# RC_module.net
KiCad netlist of a schematic drawn in EAGLE
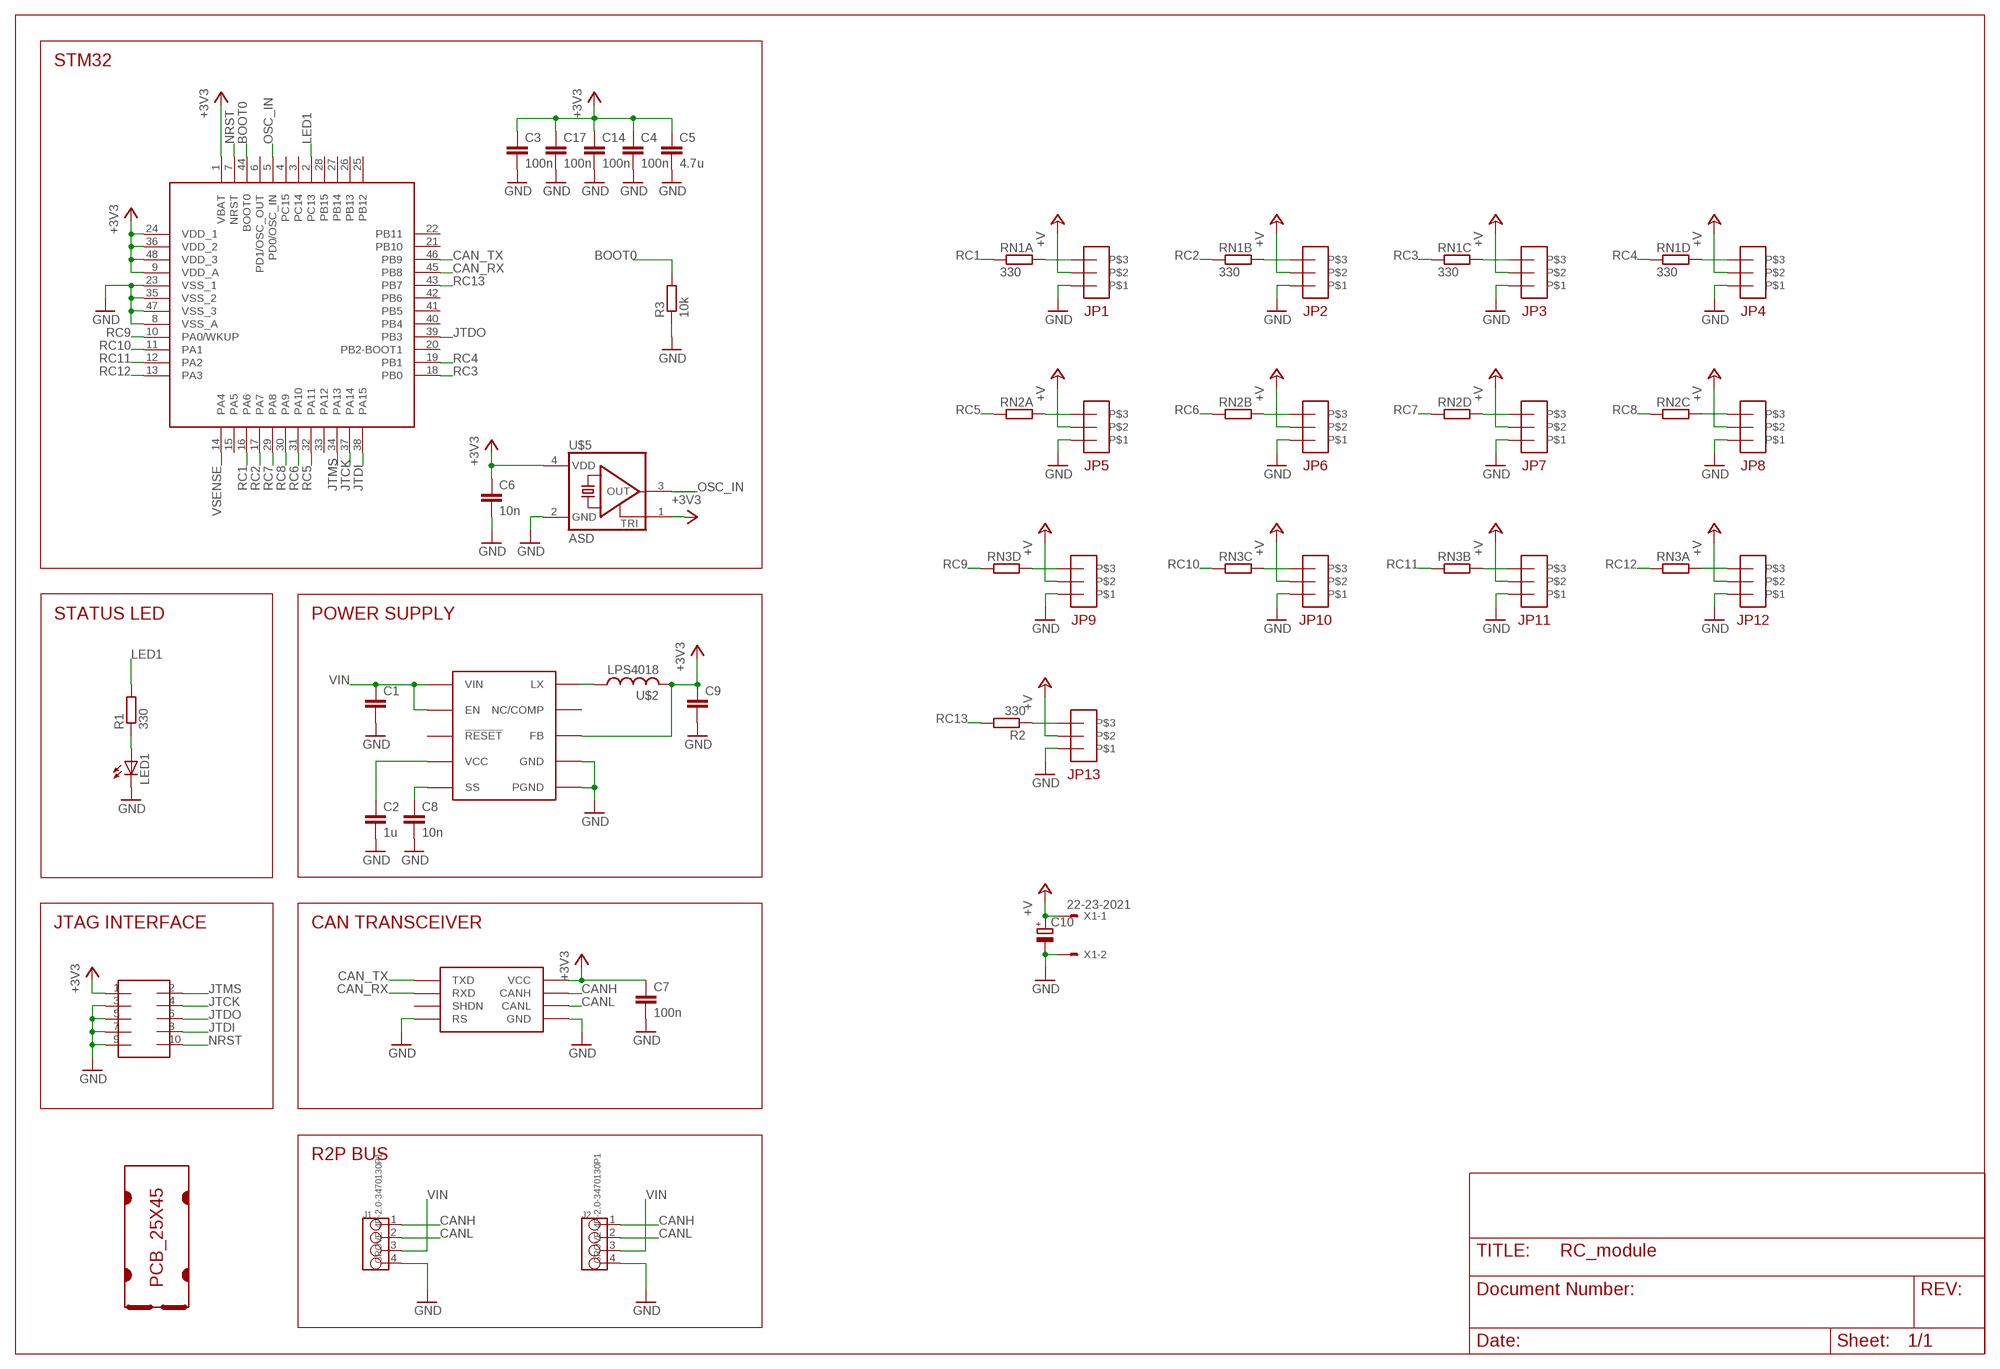
[diagram p0: schematic, sheet 1]

(export (version "E")
  (design (tool "Eeschema 10.0.6"))
  (components
    (comp (ref "C1")
      (value "C-EUC1206")
      (footprint "eagle-import:C1206")
      (libsource (lib "eagle-import") (part "C-EUC1206"))
    )
    (comp (ref "C2")
      (value "1u")
      (footprint "eagle-import:C0603")
      (libsource (lib "eagle-import") (part "C-EUC0603"))
    )
    (comp (ref "C3")
      (value "100n")
      (footprint "eagle-import:C0603")
      (libsource (lib "eagle-import") (part "C-EUC0603"))
    )
    (comp (ref "C4")
      (value "100n")
      (footprint "eagle-import:C0603")
      (libsource (lib "eagle-import") (part "C-EUC0603"))
    )
    (comp (ref "C5")
      (value "4.7u")
      (footprint "eagle-import:C0805")
      (libsource (lib "eagle-import") (part "C-EUC0805"))
    )
    (comp (ref "C6")
      (value "10n")
      (footprint "eagle-import:C0603")
      (libsource (lib "eagle-import") (part "C-EUC0603"))
    )
    (comp (ref "C7")
      (value "100n")
      (footprint "eagle-import:C0603")
      (libsource (lib "eagle-import") (part "C-EUC0603"))
    )
    (comp (ref "C8")
      (value "10n")
      (footprint "eagle-import:C0603")
      (libsource (lib "eagle-import") (part "C-EUC0603"))
    )
    (comp (ref "C9")
      (value "C-EUC0805")
      (footprint "eagle-import:C0805")
      (libsource (lib "eagle-import") (part "C-EUC0805"))
    )
    (comp (ref "C10")
      (value "CPOL-EUB/3528-21R")
      (footprint "eagle-import:B_3528-21R")
      (libsource (lib "eagle-import") (part "CPOL-EUB/3528-21R"))
    )
    (comp (ref "C14")
      (value "100n")
      (footprint "eagle-import:C0603")
      (libsource (lib "eagle-import") (part "C-EUC0603"))
    )
    (comp (ref "C17")
      (value "100n")
      (footprint "eagle-import:C0603")
      (libsource (lib "eagle-import") (part "C-EUC0603"))
    )
    (comp (ref "J1")
      (value "GROVE-4P-2.0-3470130P1")
      (footprint "eagle-import:4P-2.0")
      (libsource (lib "eagle-import") (part "GROVE-4P-2.0-3470130P1"))
    )
    (comp (ref "J2")
      (value "GROVE-4P-2.0-3470130P1")
      (footprint "eagle-import:4P-2.0")
      (libsource (lib "eagle-import") (part "GROVE-4P-2.0-3470130P1"))
    )
    (comp (ref "JP1")
      (value "PINHD-3")
      (footprint "eagle-import:1X03")
      (libsource (lib "eagle-import") (part "PINHD-3"))
    )
    (comp (ref "JP2")
      (value "PINHD-3")
      (footprint "eagle-import:1X03")
      (libsource (lib "eagle-import") (part "PINHD-3"))
    )
    (comp (ref "JP3")
      (value "PINHD-3")
      (footprint "eagle-import:1X03")
      (libsource (lib "eagle-import") (part "PINHD-3"))
    )
    (comp (ref "JP4")
      (value "PINHD-3")
      (footprint "eagle-import:1X03")
      (libsource (lib "eagle-import") (part "PINHD-3"))
    )
    (comp (ref "JP5")
      (value "PINHD-3")
      (footprint "eagle-import:1X03")
      (libsource (lib "eagle-import") (part "PINHD-3"))
    )
    (comp (ref "JP6")
      (value "PINHD-3")
      (footprint "eagle-import:1X03")
      (libsource (lib "eagle-import") (part "PINHD-3"))
    )
    (comp (ref "JP7")
      (value "PINHD-3")
      (footprint "eagle-import:1X03")
      (libsource (lib "eagle-import") (part "PINHD-3"))
    )
    (comp (ref "JP8")
      (value "PINHD-3")
      (footprint "eagle-import:1X03")
      (libsource (lib "eagle-import") (part "PINHD-3"))
    )
    (comp (ref "JP9")
      (value "PINHD-3")
      (footprint "eagle-import:1X03")
      (libsource (lib "eagle-import") (part "PINHD-3"))
    )
    (comp (ref "JP10")
      (value "PINHD-3")
      (footprint "eagle-import:1X03")
      (libsource (lib "eagle-import") (part "PINHD-3"))
    )
    (comp (ref "JP11")
      (value "PINHD-3")
      (footprint "eagle-import:1X03")
      (libsource (lib "eagle-import") (part "PINHD-3"))
    )
    (comp (ref "JP12")
      (value "PINHD-3")
      (footprint "eagle-import:1X03")
      (libsource (lib "eagle-import") (part "PINHD-3"))
    )
    (comp (ref "JP13")
      (value "PINHD-3")
      (footprint "eagle-import:1X03")
      (libsource (lib "eagle-import") (part "PINHD-3"))
    )
    (comp (ref "LED1")
      (value "LEDCHIPLED_0805")
      (footprint "eagle-import:CHIPLED_0805")
      (libsource (lib "eagle-import") (part "LEDCHIPLED_0805"))
    )
    (comp (ref "R1")
      (value "330")
      (footprint "eagle-import:R0603")
      (libsource (lib "eagle-import") (part "R-EU_R0603"))
    )
    (comp (ref "R2")
      (value "330")
      (footprint "eagle-import:R0603")
      (libsource (lib "eagle-import") (part "R-EU_R0603"))
    )
    (comp (ref "R3")
      (value "10k")
      (footprint "eagle-import:R0603")
      (libsource (lib "eagle-import") (part "R-EU_R0603"))
    )
    (comp (ref "RN1")
      (value "330")
      (footprint "eagle-import:RN8P-4R-CRA06S")
      (libsource (lib "eagle-import") (part "RESISTOR_ARRAY_4"))
    )
    (comp (ref "RN2")
      (value "RESISTOR_ARRAY_4")
      (footprint "eagle-import:RN8P-4R-CRA06S")
      (libsource (lib "eagle-import") (part "RESISTOR_ARRAY_4"))
    )
    (comp (ref "RN3")
      (value "RESISTOR_ARRAY_4")
      (footprint "eagle-import:RN8P-4R-CRA06S")
      (libsource (lib "eagle-import") (part "RESISTOR_ARRAY_4"))
    )
    (comp (ref "SOT1")
      (value "MAX3051EKA")
      (footprint "eagle-import:SOT23-8L")
      (libsource (lib "eagle-import") (part "MAX3051EKA"))
    )
    (comp (ref "U$1")
      (value "PCB_25X45")
      (footprint "eagle-import:25X45")
      (libsource (lib "eagle-import") (part "PCB_25X45"))
    )
    (comp (ref "U$2")
      (value "LPS4018")
      (footprint "eagle-import:LPS4018")
      (libsource (lib "eagle-import") (part "LPS4018"))
    )
    (comp (ref "U$3")
      (value "MAX17501")
      (footprint "eagle-import:TDFN-10")
      (libsource (lib "eagle-import") (part "MAX17501"))
    )
    (comp (ref "U$4")
      (value "FTSH-105TH")
      (footprint "eagle-import:FTSH-105-TH")
      (libsource (lib "eagle-import") (part "FTSH-105TH"))
    )
    (comp (ref "U$5")
      (value "ASD")
      (footprint "eagle-import:2.5X2")
      (libsource (lib "eagle-import") (part "ASD"))
    )
    (comp (ref "U$6")
      (value "STM32F103CX")
      (footprint "eagle-import:LQFP48")
      (libsource (lib "eagle-import") (part "STM32F103CX"))
    )
    (comp (ref "X1")
      (value "22-23-2021")
      (footprint "eagle-import:22-23-2021")
      (fields (field (name "MF") "MOLEX"))
      (libsource (lib "eagle-import") (part "22-23-2021"))
    )
  )
  (nets
    (net (code "1") (name "+3V3") (class "Default")
      (node (ref "C14") (pin "1") (pinfunction "1_1") (pintype "passive"))
      (node (ref "C17") (pin "1") (pinfunction "1_1") (pintype "passive"))
      (node (ref "C3") (pin "1") (pinfunction "1_1") (pintype "passive"))
      (node (ref "C4") (pin "1") (pinfunction "1_1") (pintype "passive"))
      (node (ref "C5") (pin "1") (pinfunction "1_1") (pintype "passive"))
      (node (ref "C6") (pin "1") (pinfunction "1_1") (pintype "passive"))
      (node (ref "C7") (pin "1") (pinfunction "1_1") (pintype "passive"))
      (node (ref "C9") (pin "1") (pinfunction "1_1") (pintype "passive"))
      (node (ref "SOT1") (pin "3") (pinfunction "VCC_3") (pintype "bidirectional"))
      (node (ref "U$2") (pin "P$2") (pinfunction "2_P$2") (pintype "passive"))
      (node (ref "U$3") (pin "P$5") (pinfunction "FB_P$5") (pintype "bidirectional"))
      (node (ref "U$4") (pin "1") (pinfunction "P$1_1") (pintype "bidirectional"))
      (node (ref "U$5") (pin "1") (pinfunction "TRI_1") (pintype "input"))
      (node (ref "U$5") (pin "4") (pinfunction "VDD_4") (pintype "power_in"))
      (node (ref "U$6") (pin "1") (pinfunction "VBAT_1") (pintype "bidirectional"))
      (node (ref "U$6") (pin "24") (pinfunction "VDD_1_24") (pintype "bidirectional"))
      (node (ref "U$6") (pin "36") (pinfunction "VDD_2_36") (pintype "bidirectional"))
      (node (ref "U$6") (pin "48") (pinfunction "VDD_3_48") (pintype "bidirectional"))
      (node (ref "U$6") (pin "9") (pinfunction "VDD_A_9") (pintype "bidirectional"))
    )
    (net (code "2") (name "+V") (class "Default")
      (node (ref "C10") (pin "+") (pinfunction "+_+") (pintype "passive"))
      (node (ref "JP1") (pin "2") (pinfunction "P$2_2") (pintype "bidirectional"))
      (node (ref "JP10") (pin "2") (pinfunction "P$2_2") (pintype "bidirectional"))
      (node (ref "JP11") (pin "2") (pinfunction "P$2_2") (pintype "bidirectional"))
      (node (ref "JP12") (pin "2") (pinfunction "P$2_2") (pintype "bidirectional"))
      (node (ref "JP13") (pin "2") (pinfunction "P$2_2") (pintype "bidirectional"))
      (node (ref "JP2") (pin "2") (pinfunction "P$2_2") (pintype "bidirectional"))
      (node (ref "JP3") (pin "2") (pinfunction "P$2_2") (pintype "bidirectional"))
      (node (ref "JP4") (pin "2") (pinfunction "P$2_2") (pintype "bidirectional"))
      (node (ref "JP5") (pin "2") (pinfunction "P$2_2") (pintype "bidirectional"))
      (node (ref "JP6") (pin "2") (pinfunction "P$2_2") (pintype "bidirectional"))
      (node (ref "JP7") (pin "2") (pinfunction "P$2_2") (pintype "bidirectional"))
      (node (ref "JP8") (pin "2") (pinfunction "P$2_2") (pintype "bidirectional"))
      (node (ref "JP9") (pin "2") (pinfunction "P$2_2") (pintype "bidirectional"))
      (node (ref "X1") (pin "1") (pinfunction "S_1") (pintype "passive"))
    )
    (net (code "3") (name "/BOOT0") (class "Default")
      (node (ref "R3") (pin "2") (pinfunction "2_2") (pintype "passive"))
      (node (ref "U$6") (pin "44") (pinfunction "BOOT0_44") (pintype "bidirectional"))
    )
    (net (code "4") (name "/CANH") (class "Default")
      (node (ref "J1") (pin "1") (pinfunction "1_1") (pintype "bidirectional"))
      (node (ref "J2") (pin "1") (pinfunction "1_1") (pintype "bidirectional"))
      (node (ref "SOT1") (pin "7") (pinfunction "CANH_7") (pintype "bidirectional"))
    )
    (net (code "5") (name "/CANL") (class "Default")
      (node (ref "J1") (pin "2") (pinfunction "2_2") (pintype "bidirectional"))
      (node (ref "J2") (pin "2") (pinfunction "2_2") (pintype "bidirectional"))
      (node (ref "SOT1") (pin "6") (pinfunction "CANL_6") (pintype "bidirectional"))
    )
    (net (code "6") (name "/CAN_RX") (class "Default")
      (node (ref "SOT1") (pin "4") (pinfunction "RXD_4") (pintype "bidirectional"))
      (node (ref "U$6") (pin "45") (pinfunction "PB8_45") (pintype "bidirectional"))
    )
    (net (code "7") (name "/CAN_TX") (class "Default")
      (node (ref "SOT1") (pin "1") (pinfunction "TXD_1") (pintype "bidirectional"))
      (node (ref "U$6") (pin "46") (pinfunction "PB9_46") (pintype "bidirectional"))
    )
    (net (code "8") (name "/JTCK") (class "Default")
      (node (ref "U$4") (pin "4") (pinfunction "P$4_4") (pintype "bidirectional"))
      (node (ref "U$6") (pin "37") (pinfunction "PA14_37") (pintype "bidirectional"))
    )
    (net (code "9") (name "/JTDI") (class "Default")
      (node (ref "U$4") (pin "8") (pinfunction "P$8_8") (pintype "bidirectional"))
      (node (ref "U$6") (pin "38") (pinfunction "PA15_38") (pintype "bidirectional"))
    )
    (net (code "10") (name "/JTDO") (class "Default")
      (node (ref "U$4") (pin "6") (pinfunction "P$6_6") (pintype "bidirectional"))
      (node (ref "U$6") (pin "39") (pinfunction "PB3_39") (pintype "bidirectional"))
    )
    (net (code "11") (name "/JTMS") (class "Default")
      (node (ref "U$4") (pin "2") (pinfunction "P$2_2") (pintype "bidirectional"))
      (node (ref "U$6") (pin "34") (pinfunction "PA13_34") (pintype "bidirectional"))
    )
    (net (code "12") (name "/LED1") (class "Default")
      (node (ref "R1") (pin "2") (pinfunction "2_2") (pintype "passive"))
      (node (ref "U$6") (pin "2") (pinfunction "PC13_2") (pintype "bidirectional"))
    )
    (net (code "13") (name "/NRST") (class "Default")
      (node (ref "U$4") (pin "10") (pinfunction "P$10_10") (pintype "bidirectional"))
      (node (ref "U$6") (pin "7") (pinfunction "NRST_7") (pintype "bidirectional"))
    )
    (net (code "14") (name "/OSC_IN") (class "Default")
      (node (ref "U$5") (pin "3") (pinfunction "OUT_3") (pintype "output"))
      (node (ref "U$6") (pin "5") (pinfunction "PD0/OSC_IN_5") (pintype "bidirectional"))
    )
    (net (code "15") (name "/RC1") (class "Default")
      (node (ref "RN1") (pin "1") (pinfunction "1_1") (pintype "passive"))
      (node (ref "U$6") (pin "16") (pinfunction "PA6_16") (pintype "bidirectional"))
    )
    (net (code "16") (name "/RC2") (class "Default")
      (node (ref "RN1") (pin "2") (pinfunction "1_2") (pintype "passive"))
      (node (ref "U$6") (pin "17") (pinfunction "PA7_17") (pintype "bidirectional"))
    )
    (net (code "17") (name "/RC3") (class "Default")
      (node (ref "RN1") (pin "3") (pinfunction "1_3") (pintype "passive"))
      (node (ref "U$6") (pin "18") (pinfunction "PB0_18") (pintype "bidirectional"))
    )
    (net (code "18") (name "/RC4") (class "Default")
      (node (ref "RN1") (pin "4") (pinfunction "1_4") (pintype "passive"))
      (node (ref "U$6") (pin "19") (pinfunction "PB1_19") (pintype "bidirectional"))
    )
    (net (code "19") (name "/RC5") (class "Default")
      (node (ref "RN2") (pin "1") (pinfunction "1_1") (pintype "passive"))
      (node (ref "U$6") (pin "32") (pinfunction "PA11_32") (pintype "bidirectional"))
    )
    (net (code "20") (name "/RC6") (class "Default")
      (node (ref "RN2") (pin "2") (pinfunction "1_2") (pintype "passive"))
      (node (ref "U$6") (pin "31") (pinfunction "PA10_31") (pintype "bidirectional"))
    )
    (net (code "21") (name "/RC7") (class "Default")
      (node (ref "RN2") (pin "4") (pinfunction "1_4") (pintype "passive"))
      (node (ref "U$6") (pin "29") (pinfunction "PA8_29") (pintype "bidirectional"))
    )
    (net (code "22") (name "/RC8") (class "Default")
      (node (ref "RN2") (pin "3") (pinfunction "1_3") (pintype "passive"))
      (node (ref "U$6") (pin "30") (pinfunction "PA9_30") (pintype "bidirectional"))
    )
    (net (code "23") (name "/RC9") (class "Default")
      (node (ref "RN3") (pin "4") (pinfunction "1_4") (pintype "passive"))
      (node (ref "U$6") (pin "10") (pinfunction "PA0/WKUP_10") (pintype "bidirectional"))
    )
    (net (code "24") (name "/RC10") (class "Default")
      (node (ref "RN3") (pin "3") (pinfunction "1_3") (pintype "passive"))
      (node (ref "U$6") (pin "11") (pinfunction "PA1_11") (pintype "bidirectional"))
    )
    (net (code "25") (name "/RC11") (class "Default")
      (node (ref "RN3") (pin "2") (pinfunction "1_2") (pintype "passive"))
      (node (ref "U$6") (pin "12") (pinfunction "PA2_12") (pintype "bidirectional"))
    )
    (net (code "26") (name "/RC12") (class "Default")
      (node (ref "RN3") (pin "1") (pinfunction "1_1") (pintype "passive"))
      (node (ref "U$6") (pin "13") (pinfunction "PA3_13") (pintype "bidirectional"))
    )
    (net (code "27") (name "/RC13") (class "Default")
      (node (ref "R2") (pin "2") (pinfunction "2_2") (pintype "passive"))
      (node (ref "U$6") (pin "43") (pinfunction "PB7_43") (pintype "bidirectional"))
    )
    (net (code "28") (name "/VIN") (class "Default")
      (node (ref "C1") (pin "1") (pinfunction "1_1") (pintype "passive"))
      (node (ref "J1") (pin "3") (pinfunction "3_3") (pintype "bidirectional"))
      (node (ref "J2") (pin "3") (pinfunction "3_3") (pintype "bidirectional"))
      (node (ref "U$3") (pin "P$2") (pinfunction "VIN_P$2") (pintype "bidirectional"))
      (node (ref "U$3") (pin "P$3") (pinfunction "EN_P$3") (pintype "bidirectional"))
    )
    (net (code "29") (name "/VSENSE") (class "Default")
      (node (ref "U$6") (pin "14") (pinfunction "PA4_14") (pintype "bidirectional"))
    )
    (net (code "30") (name "GND") (class "Default")
      (node (ref "C1") (pin "2") (pinfunction "2_2") (pintype "passive"))
      (node (ref "C10") (pin "-") (pinfunction "-_-") (pintype "passive"))
      (node (ref "C14") (pin "2") (pinfunction "2_2") (pintype "passive"))
      (node (ref "C17") (pin "2") (pinfunction "2_2") (pintype "passive"))
      (node (ref "C2") (pin "2") (pinfunction "2_2") (pintype "passive"))
      (node (ref "C3") (pin "2") (pinfunction "2_2") (pintype "passive"))
      (node (ref "C4") (pin "2") (pinfunction "2_2") (pintype "passive"))
      (node (ref "C5") (pin "2") (pinfunction "2_2") (pintype "passive"))
      (node (ref "C6") (pin "2") (pinfunction "2_2") (pintype "passive"))
      (node (ref "C7") (pin "2") (pinfunction "2_2") (pintype "passive"))
      (node (ref "C8") (pin "2") (pinfunction "2_2") (pintype "passive"))
      (node (ref "C9") (pin "2") (pinfunction "2_2") (pintype "passive"))
      (node (ref "J1") (pin "4") (pinfunction "4_4") (pintype "bidirectional"))
      (node (ref "J2") (pin "4") (pinfunction "4_4") (pintype "bidirectional"))
      (node (ref "JP1") (pin "1") (pinfunction "P$1_1") (pintype "bidirectional"))
      (node (ref "JP10") (pin "1") (pinfunction "P$1_1") (pintype "bidirectional"))
      (node (ref "JP11") (pin "1") (pinfunction "P$1_1") (pintype "bidirectional"))
      (node (ref "JP12") (pin "1") (pinfunction "P$1_1") (pintype "bidirectional"))
      (node (ref "JP13") (pin "1") (pinfunction "P$1_1") (pintype "bidirectional"))
      (node (ref "JP2") (pin "1") (pinfunction "P$1_1") (pintype "bidirectional"))
      (node (ref "JP3") (pin "1") (pinfunction "P$1_1") (pintype "bidirectional"))
      (node (ref "JP4") (pin "1") (pinfunction "P$1_1") (pintype "bidirectional"))
      (node (ref "JP5") (pin "1") (pinfunction "P$1_1") (pintype "bidirectional"))
      (node (ref "JP6") (pin "1") (pinfunction "P$1_1") (pintype "bidirectional"))
      (node (ref "JP7") (pin "1") (pinfunction "P$1_1") (pintype "bidirectional"))
      (node (ref "JP8") (pin "1") (pinfunction "P$1_1") (pintype "bidirectional"))
      (node (ref "JP9") (pin "1") (pinfunction "P$1_1") (pintype "bidirectional"))
      (node (ref "LED1") (pin "C") (pinfunction "C_C") (pintype "passive"))
      (node (ref "R3") (pin "1") (pinfunction "1_1") (pintype "passive"))
      (node (ref "SOT1") (pin "2") (pinfunction "GND_2") (pintype "bidirectional"))
      (node (ref "SOT1") (pin "8") (pinfunction "RS_8") (pintype "bidirectional"))
      (node (ref "U$3") (pin "P$1") (pinfunction "PGND_P$1") (pintype "bidirectional"))
      (node (ref "U$3") (pin "P$11") (pinfunction "PGND_P$11") (pintype "bidirectional"))
      (node (ref "U$3") (pin "P$9") (pinfunction "GND_P$9") (pintype "bidirectional"))
      (node (ref "U$4") (pin "3") (pinfunction "P$3_3") (pintype "bidirectional"))
      (node (ref "U$4") (pin "5") (pinfunction "P$5_5") (pintype "bidirectional"))
      (node (ref "U$4") (pin "7") (pinfunction "P$7_7") (pintype "bidirectional"))
      (node (ref "U$4") (pin "9") (pinfunction "P$9_9") (pintype "bidirectional"))
      (node (ref "U$5") (pin "2") (pinfunction "GND_2") (pintype "power_in"))
      (node (ref "U$6") (pin "23") (pinfunction "VSS_1_23") (pintype "bidirectional"))
      (node (ref "U$6") (pin "35") (pinfunction "VSS_2_35") (pintype "bidirectional"))
      (node (ref "U$6") (pin "47") (pinfunction "VSS_3_47") (pintype "bidirectional"))
      (node (ref "U$6") (pin "8") (pinfunction "VSS_A_8") (pintype "bidirectional"))
      (node (ref "X1") (pin "2") (pinfunction "S_2") (pintype "passive"))
    )
    (net (code "31") (name "Net-(JP1-P$3)") (class "Default")
      (node (ref "JP1") (pin "3") (pinfunction "P$3_3") (pintype "bidirectional"))
      (node (ref "RN1") (pin "8") (pinfunction "2_8") (pintype "passive"))
    )
    (net (code "32") (name "Net-(JP2-P$3)") (class "Default")
      (node (ref "JP2") (pin "3") (pinfunction "P$3_3") (pintype "bidirectional"))
      (node (ref "RN1") (pin "7") (pinfunction "2_7") (pintype "passive"))
    )
    (net (code "33") (name "Net-(JP3-P$3)") (class "Default")
      (node (ref "JP3") (pin "3") (pinfunction "P$3_3") (pintype "bidirectional"))
      (node (ref "RN1") (pin "6") (pinfunction "2_6") (pintype "passive"))
    )
    (net (code "34") (name "Net-(JP4-P$3)") (class "Default")
      (node (ref "JP4") (pin "3") (pinfunction "P$3_3") (pintype "bidirectional"))
      (node (ref "RN1") (pin "5") (pinfunction "2_5") (pintype "passive"))
    )
    (net (code "35") (name "Net-(JP5-P$3)") (class "Default")
      (node (ref "JP5") (pin "3") (pinfunction "P$3_3") (pintype "bidirectional"))
      (node (ref "RN2") (pin "8") (pinfunction "2_8") (pintype "passive"))
    )
    (net (code "36") (name "Net-(JP6-P$3)") (class "Default")
      (node (ref "JP6") (pin "3") (pinfunction "P$3_3") (pintype "bidirectional"))
      (node (ref "RN2") (pin "7") (pinfunction "2_7") (pintype "passive"))
    )
    (net (code "37") (name "Net-(JP7-P$3)") (class "Default")
      (node (ref "JP7") (pin "3") (pinfunction "P$3_3") (pintype "bidirectional"))
      (node (ref "RN2") (pin "5") (pinfunction "2_5") (pintype "passive"))
    )
    (net (code "38") (name "Net-(JP8-P$3)") (class "Default")
      (node (ref "JP8") (pin "3") (pinfunction "P$3_3") (pintype "bidirectional"))
      (node (ref "RN2") (pin "6") (pinfunction "2_6") (pintype "passive"))
    )
    (net (code "39") (name "Net-(JP9-P$3)") (class "Default")
      (node (ref "JP9") (pin "3") (pinfunction "P$3_3") (pintype "bidirectional"))
      (node (ref "RN3") (pin "5") (pinfunction "2_5") (pintype "passive"))
    )
    (net (code "40") (name "Net-(JP10-P$3)") (class "Default")
      (node (ref "JP10") (pin "3") (pinfunction "P$3_3") (pintype "bidirectional"))
      (node (ref "RN3") (pin "6") (pinfunction "2_6") (pintype "passive"))
    )
    (net (code "41") (name "Net-(JP11-P$3)") (class "Default")
      (node (ref "JP11") (pin "3") (pinfunction "P$3_3") (pintype "bidirectional"))
      (node (ref "RN3") (pin "7") (pinfunction "2_7") (pintype "passive"))
    )
    (net (code "42") (name "Net-(JP12-P$3)") (class "Default")
      (node (ref "JP12") (pin "3") (pinfunction "P$3_3") (pintype "bidirectional"))
      (node (ref "RN3") (pin "8") (pinfunction "2_8") (pintype "passive"))
    )
    (net (code "43") (name "Net-(JP13-P$3)") (class "Default")
      (node (ref "JP13") (pin "3") (pinfunction "P$3_3") (pintype "bidirectional"))
      (node (ref "R2") (pin "1") (pinfunction "1_1") (pintype "passive"))
    )
    (net (code "44") (name "Net-(LED1-PadA)") (class "Default")
      (node (ref "LED1") (pin "A") (pinfunction "A_A") (pintype "passive"))
      (node (ref "R1") (pin "1") (pinfunction "1_1") (pintype "passive"))
    )
    (net (code "45") (name "Net-(U$2-1)") (class "Default")
      (node (ref "U$2") (pin "P$1") (pinfunction "1_P$1") (pintype "passive"))
      (node (ref "U$3") (pin "P$10") (pinfunction "LX_P$10") (pintype "bidirectional"))
    )
    (net (code "46") (name "Net-(U$3-SS)") (class "Default")
      (node (ref "C8") (pin "1") (pinfunction "1_1") (pintype "passive"))
      (node (ref "U$3") (pin "P$6") (pinfunction "SS_P$6") (pintype "bidirectional"))
    )
    (net (code "47") (name "Net-(U$3-VCC)") (class "Default")
      (node (ref "C2") (pin "1") (pinfunction "1_1") (pintype "passive"))
      (node (ref "U$3") (pin "P$4") (pinfunction "VCC_P$4") (pintype "bidirectional"))
    )
    (net (code "48") (name "unconnected-(SOT1-SHDN-Pad5)") (class "Default")
      (node (ref "SOT1") (pin "5") (pinfunction "SHDN_5") (pintype "bidirectional"))
    )
    (net (code "49") (name "unconnected-(U$3-NC{slash}COMP-PadP$7)") (class "Default")
      (node (ref "U$3") (pin "P$7") (pinfunction "NC/COMP_P$7") (pintype "bidirectional"))
    )
    (net (code "50") (name "unconnected-(U$3-~{RESET}-PadP$8)") (class "Default")
      (node (ref "U$3") (pin "P$8") (pinfunction "~{RESET}_P$8") (pintype "bidirectional"))
    )
    (net (code "51") (name "unconnected-(U$6-PA5-Pad15)") (class "Default")
      (node (ref "U$6") (pin "15") (pinfunction "PA5_15") (pintype "bidirectional"))
    )
    (net (code "52") (name "unconnected-(U$6-PA12-Pad33)") (class "Default")
      (node (ref "U$6") (pin "33") (pinfunction "PA12_33") (pintype "bidirectional"))
    )
    (net (code "53") (name "unconnected-(U$6-PB2-BOOT1-Pad20)") (class "Default")
      (node (ref "U$6") (pin "20") (pinfunction "PB2-BOOT1_20") (pintype "bidirectional"))
    )
    (net (code "54") (name "unconnected-(U$6-PB4-Pad40)") (class "Default")
      (node (ref "U$6") (pin "40") (pinfunction "PB4_40") (pintype "bidirectional"))
    )
    (net (code "55") (name "unconnected-(U$6-PB5-Pad41)") (class "Default")
      (node (ref "U$6") (pin "41") (pinfunction "PB5_41") (pintype "bidirectional"))
    )
    (net (code "56") (name "unconnected-(U$6-PB6-Pad42)") (class "Default")
      (node (ref "U$6") (pin "42") (pinfunction "PB6_42") (pintype "bidirectional"))
    )
    (net (code "57") (name "unconnected-(U$6-PB10-Pad21)") (class "Default")
      (node (ref "U$6") (pin "21") (pinfunction "PB10_21") (pintype "bidirectional"))
    )
    (net (code "58") (name "unconnected-(U$6-PB11-Pad22)") (class "Default")
      (node (ref "U$6") (pin "22") (pinfunction "PB11_22") (pintype "bidirectional"))
    )
    (net (code "59") (name "unconnected-(U$6-PB12-Pad25)") (class "Default")
      (node (ref "U$6") (pin "25") (pinfunction "PB12_25") (pintype "bidirectional"))
    )
    (net (code "60") (name "unconnected-(U$6-PB13-Pad26)") (class "Default")
      (node (ref "U$6") (pin "26") (pinfunction "PB13_26") (pintype "bidirectional"))
    )
    (net (code "61") (name "unconnected-(U$6-PB14-Pad27)") (class "Default")
      (node (ref "U$6") (pin "27") (pinfunction "PB14_27") (pintype "bidirectional"))
    )
    (net (code "62") (name "unconnected-(U$6-PB15-Pad28)") (class "Default")
      (node (ref "U$6") (pin "28") (pinfunction "PB15_28") (pintype "bidirectional"))
    )
    (net (code "63") (name "unconnected-(U$6-PC14-Pad3)") (class "Default")
      (node (ref "U$6") (pin "3") (pinfunction "PC14_3") (pintype "bidirectional"))
    )
    (net (code "64") (name "unconnected-(U$6-PC15-Pad4)") (class "Default")
      (node (ref "U$6") (pin "4") (pinfunction "PC15_4") (pintype "bidirectional"))
    )
    (net (code "65") (name "unconnected-(U$6-PD1{slash}OSC_OUT-Pad6)") (class "Default")
      (node (ref "U$6") (pin "6") (pinfunction "PD1/OSC_OUT_6") (pintype "bidirectional"))
    )
  )
)
